# NPN_CONNECTOR.net
KiCad netlist of a schematic drawn in Altium Designer
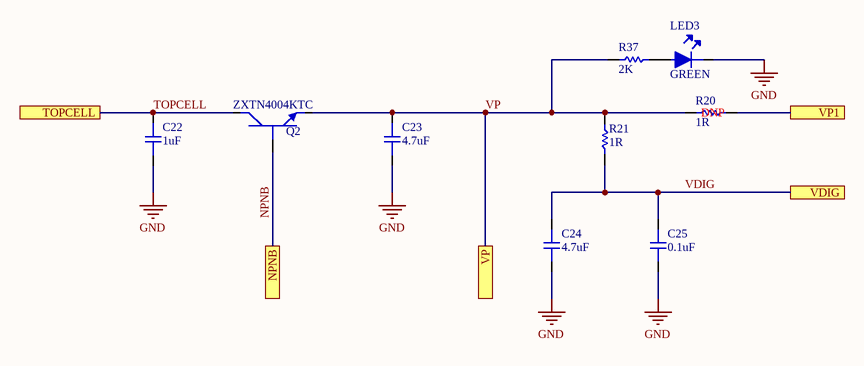
[diagram p0: NPN_CONNECTOR.SchDoc]

(export (version "E")
  (design (tool "Eeschema 10.0.6"))
  (components
    (comp (ref "C22")
      (value "1uF")
      (footprint "0805 CAP")
      (description "CAP CER 1UF 100V X7S 0805")
      (fields
        (field (name "MANUFACTURER") "TDK")
        (field (name "MANUFACTURER PART NUMBER") "C2012X7S2A105K125AE")
      )
      (libsource (lib "parts") (part "C2012X7S2A105K125AE"))
    )
    (comp (ref "C23")
      (value "4.7uF")
      (footprint "1206 CAP")
      (description "CAP CER 4.7UF 50V X7R 1206")
      (fields
        (field (name "MANUFACTURER") "Murata")
        (field (name "MANUFACTURER PART NUMBER") "GRM31CR71H475KA12L")
      )
      (libsource (lib "parts") (part "GRM31CR71H475KA12L"))
    )
    (comp (ref "C24")
      (value "4.7uF")
      (footprint "0805 CAP")
      (description "CAP CER 4.7UF 16V X7R 0805")
      (fields
        (field (name "MANUFACTURER") "Samsung")
        (field (name "MANUFACTURER PART NUMBER") "CL21B475KOFNFNE")
      )
      (libsource (lib "parts") (part "CL21B475KOFNFNE"))
    )
    (comp (ref "C25")
      (value "0.1uF")
      (footprint "0603 CAP - duplicate")
      (description "CAP CER 0.1UF 50V X7R 0603")
      (fields
        (field (name "MANUFACTURER") "Kyocera AVX")
        (field (name "MANUFACTURER PART NUMBER") "06035C104KAZ2A")
      )
      (libsource (lib "parts") (part "06035C104KAZ2A"))
    )
    (comp (ref "LED3")
      (value "GREEN")
      (footprint "LED2")
      (description "LED GREEN CLEAR 0603 SMD")
      (fields
        (field (name "MANUFACTURER") "Wurth Electronics")
        (field (name "MANUFACTURER PART NUMBER") "150060VS75000")
      )
      (libsource (lib "parts") (part "150060VS75000"))
    )
    (comp (ref "Q2")
      (value "ZXTN4004KTC")
      (footprint "NPN TRANSISTOR")
      (description "TRANS NPN 150V 1A TO252")
      (fields (field (name "MANUFACTURER") "Diodes"))
      (libsource (lib "parts") (part "ZXTN4004KTC"))
    )
    (comp (ref "R20")
      (value "1R")
      (footprint "0603 RES")
      (description "RES SMD 1 OHM 1% 1/10W 0603")
      (fields
        (field (name "MANUFACTURER") "Bourns")
        (field (name "MANUFACTURER PART NUMBER") "CRL0603-FW-1R00ELF")
      )
      (libsource (lib "parts") (part "CRL0603-FW-1R00ELF"))
    )
    (comp (ref "R21")
      (value "1R")
      (footprint "0603 RES")
      (description "RES SMD 1 OHM 1% 1/10W 0603")
      (fields
        (field (name "MANUFACTURER") "Bourns")
        (field (name "MANUFACTURER PART NUMBER") "CRL0603-FW-1R00ELF")
      )
      (libsource (lib "parts") (part "CRL0603-FW-1R00ELF"))
    )
    (comp (ref "R37")
      (value "2K")
      (footprint "0603 RES")
      (description "RES SMD 2K OHM 1% 1/10W 0603")
      (fields
        (field (name "MANUFACTURER") "Vishay")
        (field (name "MANUFACTURER PART NUMBER") "CRCW06032K00FKEA")
      )
      (libsource (lib "parts") (part "CRCW06032K00FKEA"))
    )
  )
  (nets
    (net (code "1") (name "/NPNB") (class "Default")
      (node (ref "Q2") (pin "1") (pinfunction "1_1") (pintype "passive"))
    )
    (net (code "2") (name "/TOPCELL") (class "Default")
      (node (ref "C22") (pin "2") (pinfunction "2_2") (pintype "passive"))
      (node (ref "Q2") (pin "2") (pinfunction "2_2") (pintype "passive"))
    )
    (net (code "3") (name "/VDIG") (class "Default")
      (node (ref "C24") (pin "2") (pinfunction "2_2") (pintype "passive"))
      (node (ref "C25") (pin "2") (pinfunction "2_2") (pintype "passive"))
      (node (ref "R21") (pin "1") (pinfunction "1_1") (pintype "passive"))
    )
    (net (code "4") (name "/VP") (class "Default")
      (node (ref "C23") (pin "2") (pinfunction "2_2") (pintype "passive"))
      (node (ref "Q2") (pin "3") (pinfunction "3_3") (pintype "passive"))
      (node (ref "R20") (pin "1") (pinfunction "1_1") (pintype "passive"))
      (node (ref "R21") (pin "2") (pinfunction "2_2") (pintype "passive"))
      (node (ref "R37") (pin "1") (pinfunction "1_1") (pintype "passive"))
    )
    (net (code "5") (name "/VP1") (class "Default")
      (node (ref "R20") (pin "2") (pinfunction "2_2") (pintype "passive"))
    )
    (net (code "6") (name "GND") (class "Default")
      (node (ref "C22") (pin "1") (pinfunction "1_1") (pintype "passive"))
      (node (ref "C23") (pin "1") (pinfunction "1_1") (pintype "passive"))
      (node (ref "C24") (pin "1") (pinfunction "1_1") (pintype "passive"))
      (node (ref "C25") (pin "1") (pinfunction "1_1") (pintype "passive"))
      (node (ref "LED3") (pin "2") (pinfunction "2_2") (pintype "passive"))
    )
    (net (code "7") (name "Net-(LED3-Pad1)") (class "Default")
      (node (ref "LED3") (pin "1") (pinfunction "1_1") (pintype "passive"))
      (node (ref "R37") (pin "2") (pinfunction "2_2") (pintype "passive"))
    )
  )
)
